# marty.net
KiCad netlist of a schematic drawn in EAGLE
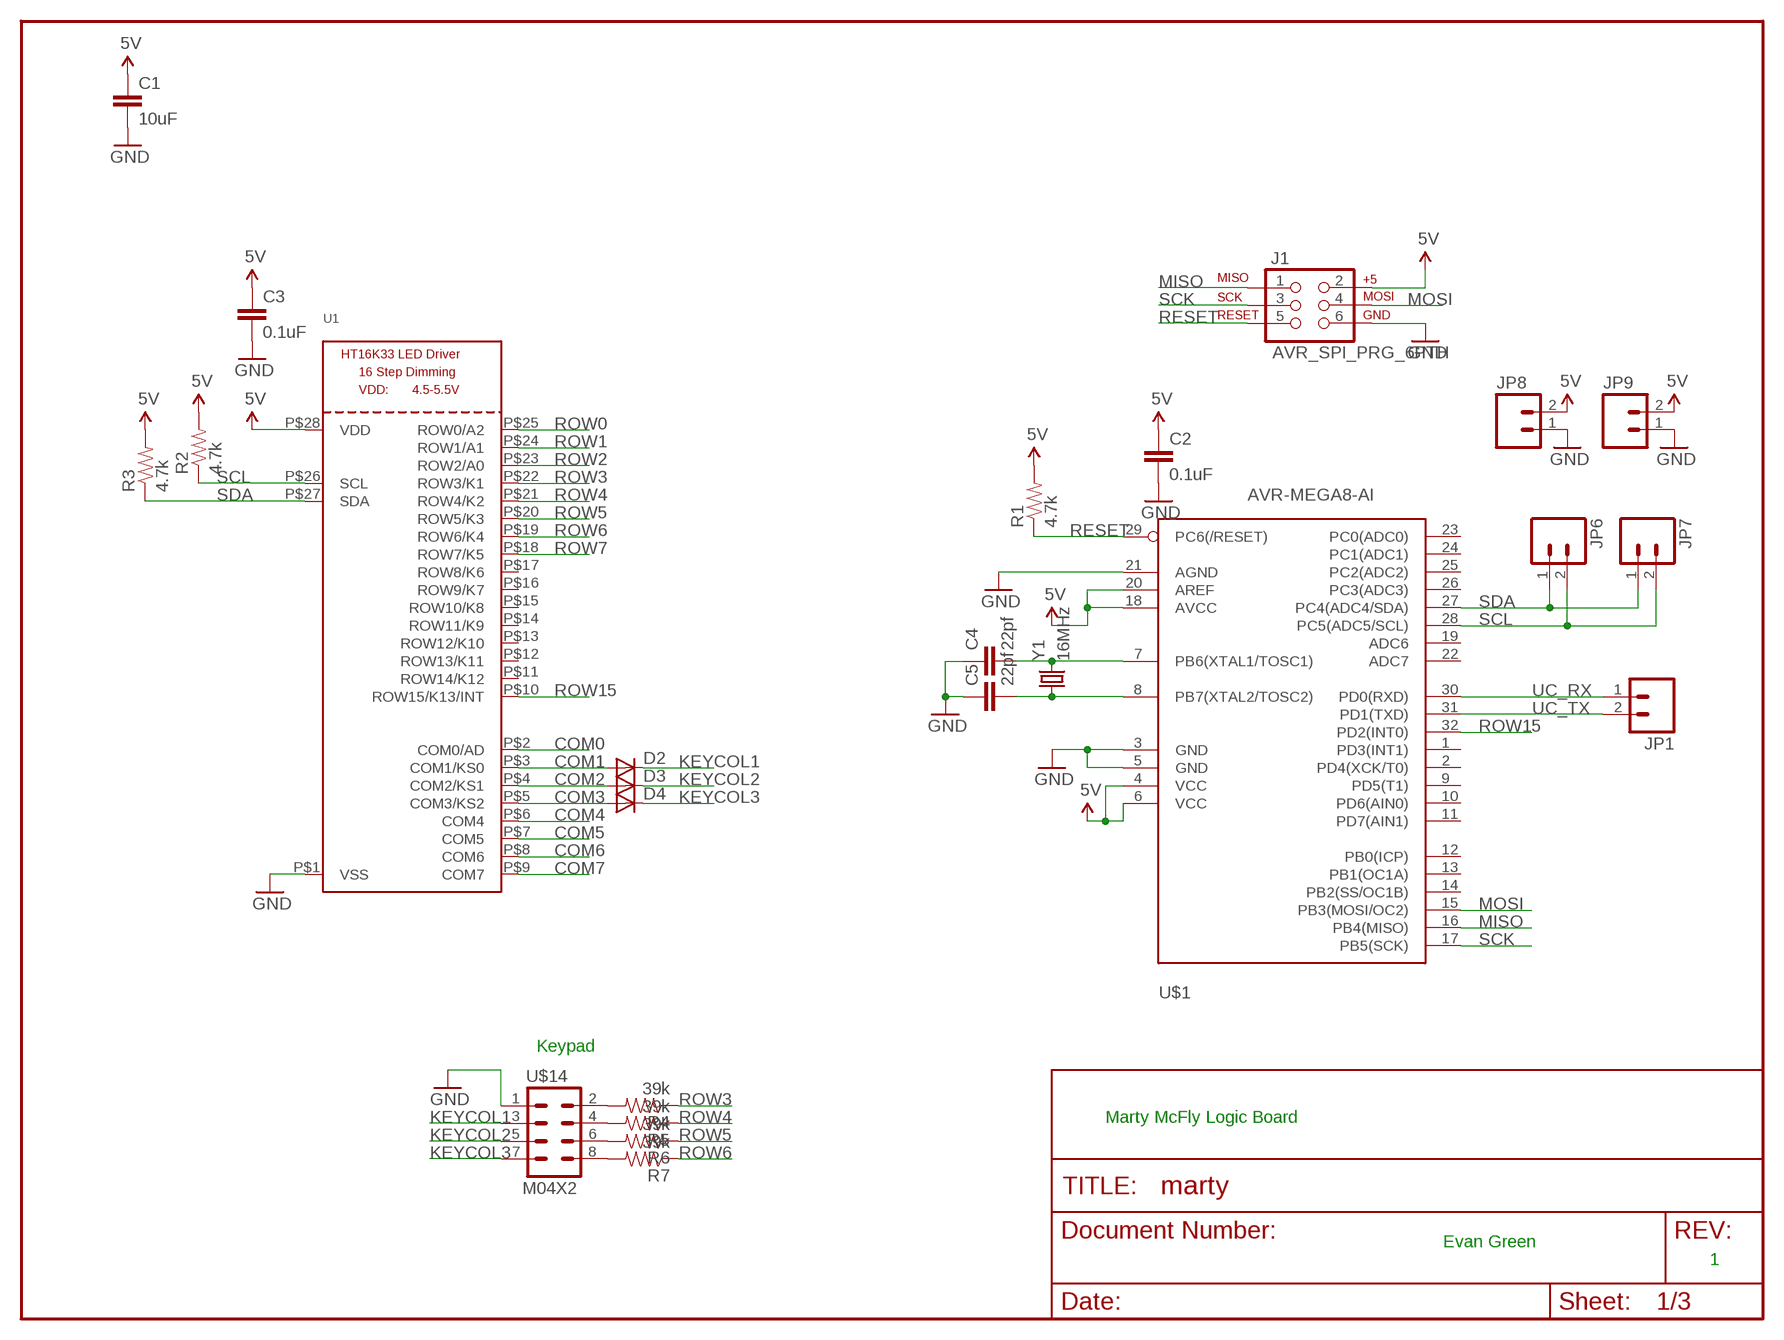
[diagram p0: schematic, sheet 1]
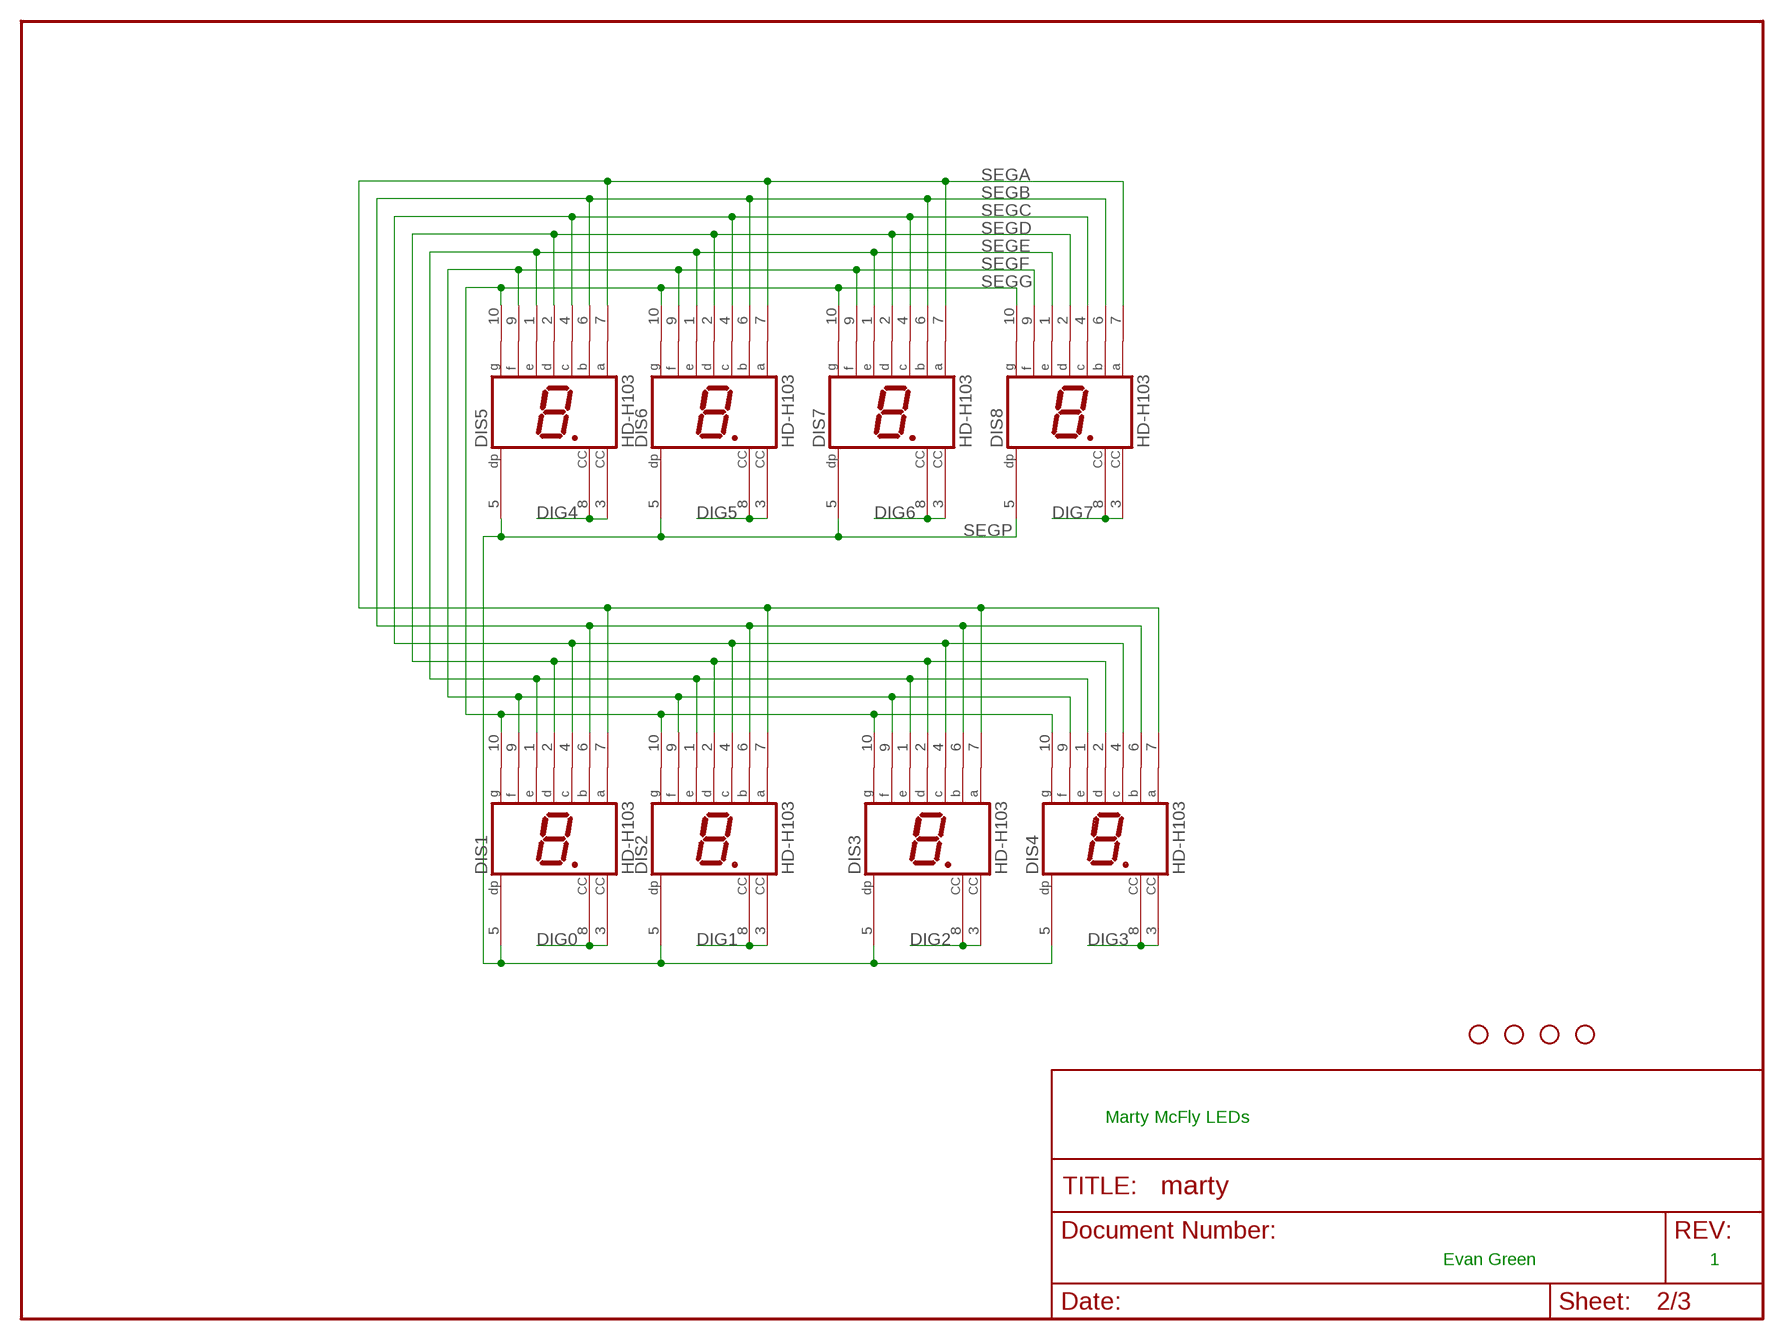
[diagram p1: schematic, sheet 2]
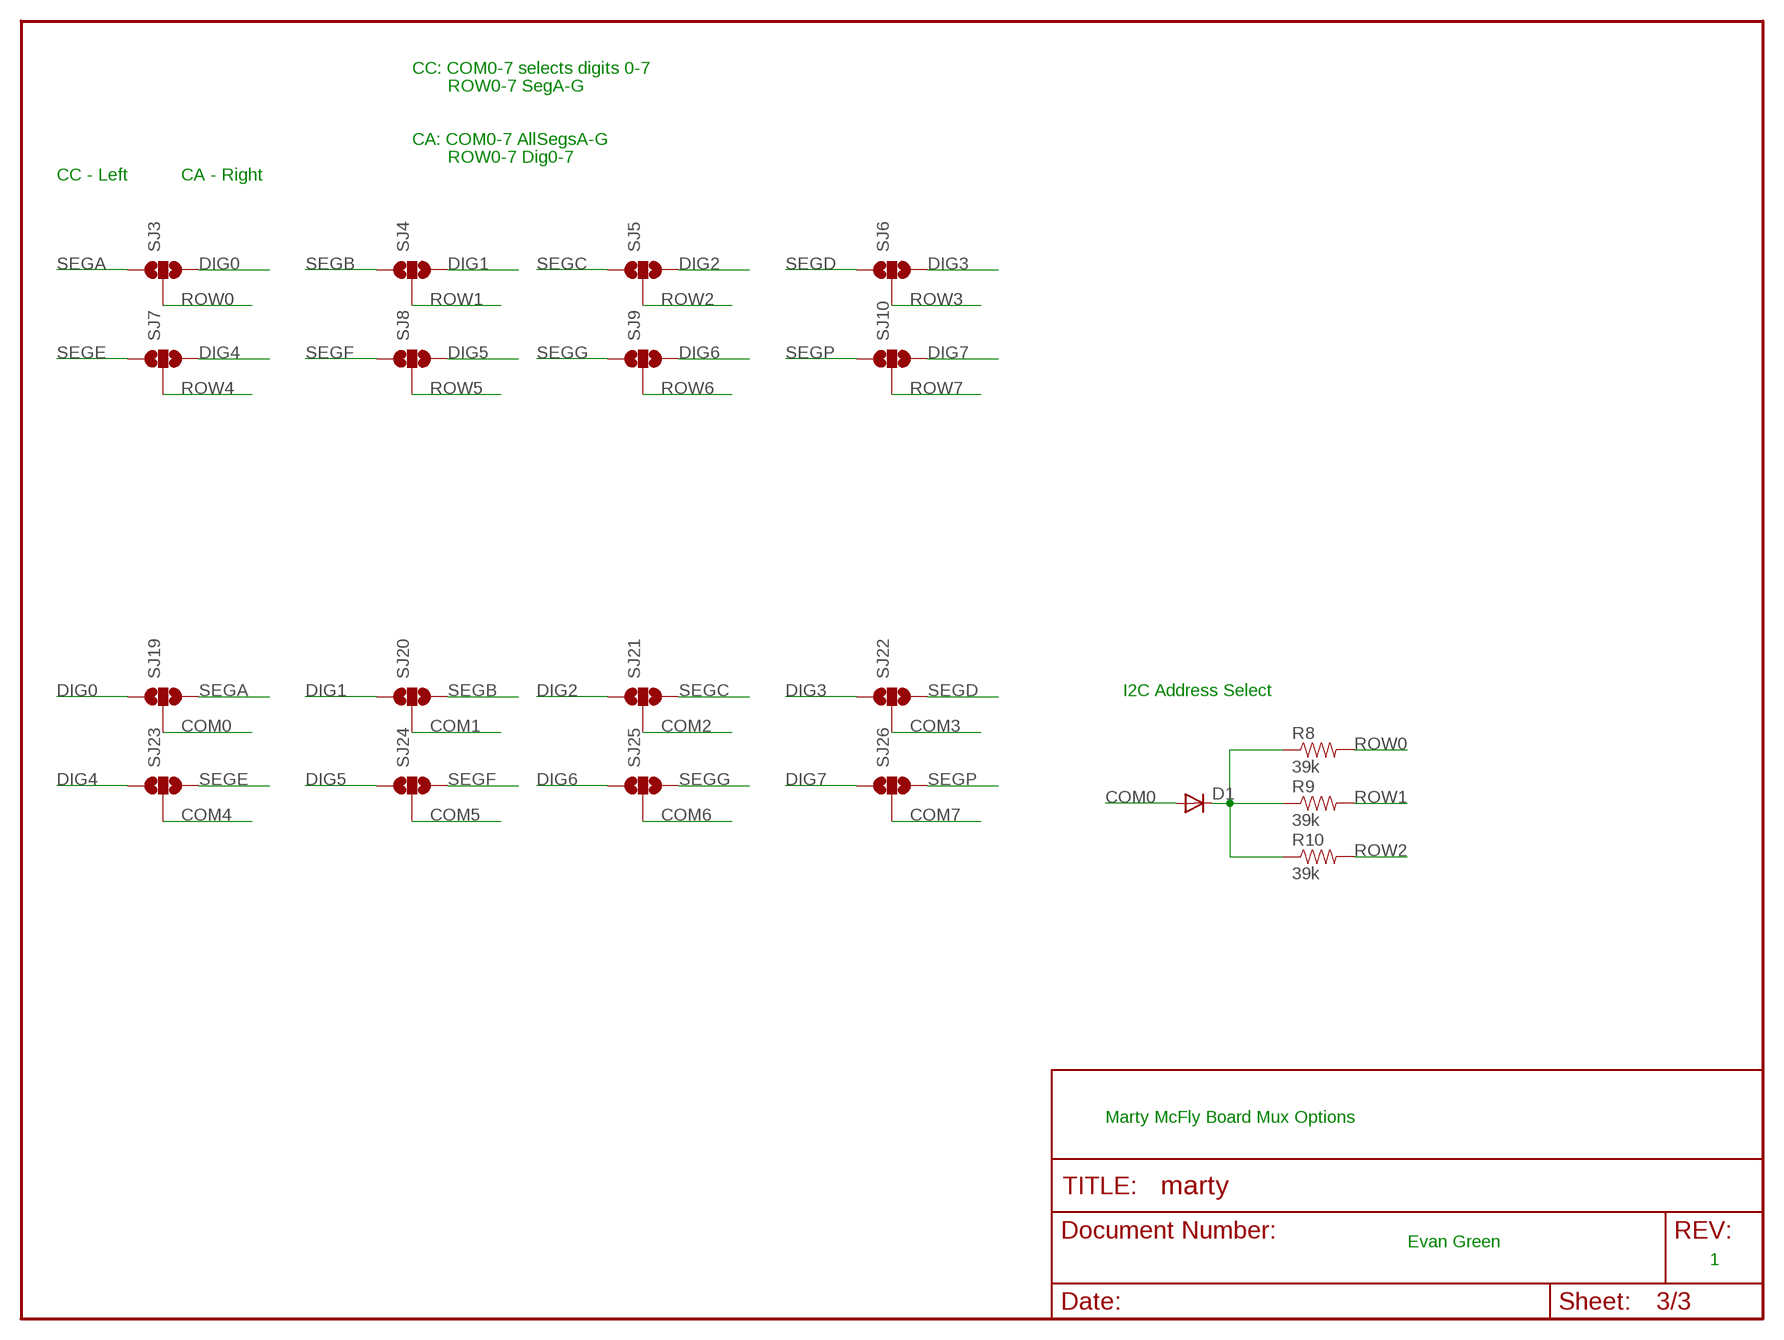
[diagram p2: schematic, sheet 3]

(export (version "E")
  (design (tool "Eeschema 10.0.6"))
  (components
    (comp (ref "C1")
      (value "10uF")
      (footprint "eagle-import:1210")
      (libsource (lib "eagle-import") (part "CAP1210"))
    )
    (comp (ref "C2")
      (value "0.1uF")
      (footprint "eagle-import:0402-CAP")
      (libsource (lib "eagle-import") (part "CAP0402-CAP"))
    )
    (comp (ref "C3")
      (value "0.1uF")
      (footprint "eagle-import:0402-CAP")
      (libsource (lib "eagle-import") (part "CAP0402-CAP"))
    )
    (comp (ref "C4")
      (value "22pf")
      (footprint "eagle-import:0402-CAP")
      (libsource (lib "eagle-import") (part "CAP0402-CAP"))
    )
    (comp (ref "C5")
      (value "22pf")
      (footprint "eagle-import:0402-CAP")
      (libsource (lib "eagle-import") (part "CAP0402-CAP"))
    )
    (comp (ref "D2")
      (value "DIODESOD")
      (footprint "eagle-import:SOD-323")
      (libsource (lib "eagle-import") (part "DIODESOD"))
    )
    (comp (ref "D3")
      (value "DIODESOD")
      (footprint "eagle-import:SOD-323")
      (libsource (lib "eagle-import") (part "DIODESOD"))
    )
    (comp (ref "D4")
      (value "DIODESOD")
      (footprint "eagle-import:SOD-323")
      (libsource (lib "eagle-import") (part "DIODESOD"))
    )
    (comp (ref "J1")
      (value "AVR_SPI_PRG_6PTH")
      (footprint "eagle-import:2X3")
      (libsource (lib "eagle-import") (part "AVR_SPI_PRG_6PTH"))
    )
    (comp (ref "JP1")
      (value "M02PTH")
      (footprint "eagle-import:1X02")
      (libsource (lib "eagle-import") (part "M02PTH"))
    )
    (comp (ref "JP6")
      (value "M02PTH")
      (footprint "eagle-import:1X02")
      (libsource (lib "eagle-import") (part "M02PTH"))
    )
    (comp (ref "JP7")
      (value "M02PTH")
      (footprint "eagle-import:1X02")
      (libsource (lib "eagle-import") (part "M02PTH"))
    )
    (comp (ref "JP8")
      (value "M02PTH")
      (footprint "eagle-import:1X02")
      (libsource (lib "eagle-import") (part "M02PTH"))
    )
    (comp (ref "JP9")
      (value "M02PTH")
      (footprint "eagle-import:1X02")
      (libsource (lib "eagle-import") (part "M02PTH"))
    )
    (comp (ref "R1")
      (value "4.7k")
      (footprint "eagle-import:0402-RES")
      (libsource (lib "eagle-import") (part "RESISTOR0402-RES"))
    )
    (comp (ref "R2")
      (value "4.7k")
      (footprint "eagle-import:0402-RES")
      (libsource (lib "eagle-import") (part "RESISTOR0402-RES"))
    )
    (comp (ref "R3")
      (value "4.7k")
      (footprint "eagle-import:0402-RES")
      (libsource (lib "eagle-import") (part "RESISTOR0402-RES"))
    )
    (comp (ref "R4")
      (value "39k")
      (footprint "eagle-import:0402-RES")
      (libsource (lib "eagle-import") (part "RESISTOR0402-RES"))
    )
    (comp (ref "R5")
      (value "39k")
      (footprint "eagle-import:0402-RES")
      (libsource (lib "eagle-import") (part "RESISTOR0402-RES"))
    )
    (comp (ref "R6")
      (value "39k")
      (footprint "eagle-import:0402-RES")
      (libsource (lib "eagle-import") (part "RESISTOR0402-RES"))
    )
    (comp (ref "R7")
      (value "39k")
      (footprint "eagle-import:0402-RES")
      (libsource (lib "eagle-import") (part "RESISTOR0402-RES"))
    )
    (comp (ref "U$1")
      (value "AVR-MEGA8-AI")
      (footprint "eagle-import:TQFP32-08")
      (libsource (lib "eagle-import") (part "AVR-MEGA8-AI"))
    )
    (comp (ref "U$14")
      (value "M04X2")
      (footprint "eagle-import:2X4")
      (libsource (lib "eagle-import") (part "M04X2"))
    )
    (comp (ref "U1")
      (value "HT16K33_SOP28")
      (footprint "eagle-import:SOP28_300MIL")
      (libsource (lib "eagle-import") (part "HT16K33_SOP28"))
    )
    (comp (ref "Y1")
      (value "16MHz")
      (footprint "eagle-import:HC49US")
      (libsource (lib "eagle-import") (part "CRYSTALHC49US"))
    )
    (comp (ref "D1")
      (value "DIODESOD")
      (footprint "eagle-import:SOD-323")
      (libsource (lib "eagle-import") (part "DIODESOD"))
    )
    (comp (ref "R8")
      (value "39k")
      (footprint "eagle-import:0402-RES")
      (libsource (lib "eagle-import") (part "RESISTOR0402-RES"))
    )
    (comp (ref "R9")
      (value "39k")
      (footprint "eagle-import:0402-RES")
      (libsource (lib "eagle-import") (part "RESISTOR0402-RES"))
    )
    (comp (ref "R10")
      (value "39k")
      (footprint "eagle-import:0402-RES")
      (libsource (lib "eagle-import") (part "RESISTOR0402-RES"))
    )
    (comp (ref "SJ3")
      (value "SOLDERJUMPER_2WAYS")
      (footprint "eagle-import:SJ_3")
      (libsource (lib "eagle-import") (part "SOLDERJUMPER_2WAYS"))
    )
    (comp (ref "SJ4")
      (value "SOLDERJUMPER_2WAYS")
      (footprint "eagle-import:SJ_3")
      (libsource (lib "eagle-import") (part "SOLDERJUMPER_2WAYS"))
    )
    (comp (ref "SJ5")
      (value "SOLDERJUMPER_2WAYS")
      (footprint "eagle-import:SJ_3")
      (libsource (lib "eagle-import") (part "SOLDERJUMPER_2WAYS"))
    )
    (comp (ref "SJ6")
      (value "SOLDERJUMPER_2WAYS")
      (footprint "eagle-import:SJ_3")
      (libsource (lib "eagle-import") (part "SOLDERJUMPER_2WAYS"))
    )
    (comp (ref "SJ7")
      (value "SOLDERJUMPER_2WAYS")
      (footprint "eagle-import:SJ_3")
      (libsource (lib "eagle-import") (part "SOLDERJUMPER_2WAYS"))
    )
    (comp (ref "SJ8")
      (value "SOLDERJUMPER_2WAYS")
      (footprint "eagle-import:SJ_3")
      (libsource (lib "eagle-import") (part "SOLDERJUMPER_2WAYS"))
    )
    (comp (ref "SJ9")
      (value "SOLDERJUMPER_2WAYS")
      (footprint "eagle-import:SJ_3")
      (libsource (lib "eagle-import") (part "SOLDERJUMPER_2WAYS"))
    )
    (comp (ref "SJ10")
      (value "SOLDERJUMPER_2WAYS")
      (footprint "eagle-import:SJ_3")
      (libsource (lib "eagle-import") (part "SOLDERJUMPER_2WAYS"))
    )
    (comp (ref "SJ19")
      (value "SOLDERJUMPER_2WAYS")
      (footprint "eagle-import:SJ_3")
      (libsource (lib "eagle-import") (part "SOLDERJUMPER_2WAYS"))
    )
    (comp (ref "SJ20")
      (value "SOLDERJUMPER_2WAYS")
      (footprint "eagle-import:SJ_3")
      (libsource (lib "eagle-import") (part "SOLDERJUMPER_2WAYS"))
    )
    (comp (ref "SJ21")
      (value "SOLDERJUMPER_2WAYS")
      (footprint "eagle-import:SJ_3")
      (libsource (lib "eagle-import") (part "SOLDERJUMPER_2WAYS"))
    )
    (comp (ref "SJ22")
      (value "SOLDERJUMPER_2WAYS")
      (footprint "eagle-import:SJ_3")
      (libsource (lib "eagle-import") (part "SOLDERJUMPER_2WAYS"))
    )
    (comp (ref "SJ23")
      (value "SOLDERJUMPER_2WAYS")
      (footprint "eagle-import:SJ_3")
      (libsource (lib "eagle-import") (part "SOLDERJUMPER_2WAYS"))
    )
    (comp (ref "SJ24")
      (value "SOLDERJUMPER_2WAYS")
      (footprint "eagle-import:SJ_3")
      (libsource (lib "eagle-import") (part "SOLDERJUMPER_2WAYS"))
    )
    (comp (ref "SJ25")
      (value "SOLDERJUMPER_2WAYS")
      (footprint "eagle-import:SJ_3")
      (libsource (lib "eagle-import") (part "SOLDERJUMPER_2WAYS"))
    )
    (comp (ref "SJ26")
      (value "SOLDERJUMPER_2WAYS")
      (footprint "eagle-import:SJ_3")
      (libsource (lib "eagle-import") (part "SOLDERJUMPER_2WAYS"))
    )
    (comp (ref "DIS1")
      (value "HD-H103")
      (footprint "eagle-import:HDSP-M")
      (libsource (lib "eagle-import") (part "HD-H103"))
    )
    (comp (ref "DIS2")
      (value "HD-H103")
      (footprint "eagle-import:HDSP-M")
      (libsource (lib "eagle-import") (part "HD-H103"))
    )
    (comp (ref "DIS3")
      (value "HD-H103")
      (footprint "eagle-import:HDSP-M")
      (libsource (lib "eagle-import") (part "HD-H103"))
    )
    (comp (ref "DIS4")
      (value "HD-H103")
      (footprint "eagle-import:HDSP-M")
      (libsource (lib "eagle-import") (part "HD-H103"))
    )
    (comp (ref "DIS5")
      (value "HD-H103")
      (footprint "eagle-import:HDSP-M")
      (libsource (lib "eagle-import") (part "HD-H103"))
    )
    (comp (ref "DIS6")
      (value "HD-H103")
      (footprint "eagle-import:HDSP-M")
      (libsource (lib "eagle-import") (part "HD-H103"))
    )
    (comp (ref "DIS7")
      (value "HD-H103")
      (footprint "eagle-import:HDSP-M")
      (libsource (lib "eagle-import") (part "HD-H103"))
    )
    (comp (ref "DIS8")
      (value "HD-H103")
      (footprint "eagle-import:HDSP-M")
      (libsource (lib "eagle-import") (part "HD-H103"))
    )
    (comp (ref "JP2")
      (value "STAND-OFF")
      (footprint "eagle-import:STAND-OFF")
      (libsource (lib "eagle-import") (part "STAND-OFF"))
    )
    (comp (ref "JP3")
      (value "STAND-OFF")
      (footprint "eagle-import:STAND-OFF")
      (libsource (lib "eagle-import") (part "STAND-OFF"))
    )
    (comp (ref "JP4")
      (value "STAND-OFF")
      (footprint "eagle-import:STAND-OFF")
      (libsource (lib "eagle-import") (part "STAND-OFF"))
    )
    (comp (ref "JP5")
      (value "STAND-OFF")
      (footprint "eagle-import:STAND-OFF")
      (libsource (lib "eagle-import") (part "STAND-OFF"))
    )
  )
  (nets
    (net (code "1") (name "5V") (class "Default")
      (node (ref "C1") (pin "1") (pinfunction "1_1") (pintype "passive"))
      (node (ref "C2") (pin "1") (pinfunction "1_1") (pintype "passive"))
      (node (ref "C3") (pin "1") (pinfunction "1_1") (pintype "passive"))
      (node (ref "J1") (pin "2") (pinfunction "2_2") (pintype "passive"))
      (node (ref "JP8") (pin "2") (pinfunction "2_2") (pintype "passive"))
      (node (ref "JP9") (pin "2") (pinfunction "2_2") (pintype "passive"))
      (node (ref "R1") (pin "2") (pinfunction "2_2") (pintype "passive"))
      (node (ref "R2") (pin "2") (pinfunction "2_2") (pintype "passive"))
      (node (ref "R3") (pin "2") (pinfunction "2_2") (pintype "passive"))
      (node (ref "U$1") (pin "18") (pinfunction "AVCC_18") (pintype "bidirectional"))
      (node (ref "U$1") (pin "20") (pinfunction "AREF_20") (pintype "bidirectional"))
      (node (ref "U$1") (pin "4") (pinfunction "VCC_4") (pintype "bidirectional"))
      (node (ref "U$1") (pin "6") (pinfunction "VCC_6") (pintype "bidirectional"))
      (node (ref "U1") (pin "P$28") (pinfunction "VDD_P$28") (pintype "bidirectional"))
    )
    (net (code "2") (name "COM0") (class "Default")
      (node (ref "D1") (pin "2") (pinfunction "A_2") (pintype "passive"))
      (node (ref "SJ19") (pin "2") (pinfunction "2_2") (pintype "passive"))
      (node (ref "U1") (pin "P$2") (pinfunction "COM0/AD_P$2") (pintype "bidirectional"))
    )
    (net (code "3") (name "COM1") (class "Default")
      (node (ref "D2") (pin "2") (pinfunction "A_2") (pintype "passive"))
      (node (ref "SJ20") (pin "2") (pinfunction "2_2") (pintype "passive"))
      (node (ref "U1") (pin "P$3") (pinfunction "COM1/KS0_P$3") (pintype "bidirectional"))
    )
    (net (code "4") (name "COM2") (class "Default")
      (node (ref "D3") (pin "2") (pinfunction "A_2") (pintype "passive"))
      (node (ref "SJ21") (pin "2") (pinfunction "2_2") (pintype "passive"))
      (node (ref "U1") (pin "P$4") (pinfunction "COM2/KS1_P$4") (pintype "bidirectional"))
    )
    (net (code "5") (name "COM3") (class "Default")
      (node (ref "D4") (pin "2") (pinfunction "A_2") (pintype "passive"))
      (node (ref "SJ22") (pin "2") (pinfunction "2_2") (pintype "passive"))
      (node (ref "U1") (pin "P$5") (pinfunction "COM3/KS2_P$5") (pintype "bidirectional"))
    )
    (net (code "6") (name "COM4") (class "Default")
      (node (ref "SJ23") (pin "2") (pinfunction "2_2") (pintype "passive"))
      (node (ref "U1") (pin "P$6") (pinfunction "COM4_P$6") (pintype "bidirectional"))
    )
    (net (code "7") (name "COM5") (class "Default")
      (node (ref "SJ24") (pin "2") (pinfunction "2_2") (pintype "passive"))
      (node (ref "U1") (pin "P$7") (pinfunction "COM5_P$7") (pintype "bidirectional"))
    )
    (net (code "8") (name "COM6") (class "Default")
      (node (ref "SJ25") (pin "2") (pinfunction "2_2") (pintype "passive"))
      (node (ref "U1") (pin "P$8") (pinfunction "COM6_P$8") (pintype "bidirectional"))
    )
    (net (code "9") (name "COM7") (class "Default")
      (node (ref "SJ26") (pin "2") (pinfunction "2_2") (pintype "passive"))
      (node (ref "U1") (pin "P$9") (pinfunction "COM7_P$9") (pintype "bidirectional"))
    )
    (net (code "10") (name "DIG0") (class "Default")
      (node (ref "DIS1") (pin "3") (pinfunction "CC_3") (pintype "passive"))
      (node (ref "DIS1") (pin "8") (pinfunction "CC_8") (pintype "passive"))
      (node (ref "SJ19") (pin "1") (pinfunction "1_1") (pintype "passive"))
      (node (ref "SJ3") (pin "3") (pinfunction "3_3") (pintype "passive"))
    )
    (net (code "11") (name "DIG1") (class "Default")
      (node (ref "DIS2") (pin "3") (pinfunction "CC_3") (pintype "passive"))
      (node (ref "DIS2") (pin "8") (pinfunction "CC_8") (pintype "passive"))
      (node (ref "SJ20") (pin "1") (pinfunction "1_1") (pintype "passive"))
      (node (ref "SJ4") (pin "3") (pinfunction "3_3") (pintype "passive"))
    )
    (net (code "12") (name "DIG2") (class "Default")
      (node (ref "DIS3") (pin "3") (pinfunction "CC_3") (pintype "passive"))
      (node (ref "DIS3") (pin "8") (pinfunction "CC_8") (pintype "passive"))
      (node (ref "SJ21") (pin "1") (pinfunction "1_1") (pintype "passive"))
      (node (ref "SJ5") (pin "3") (pinfunction "3_3") (pintype "passive"))
    )
    (net (code "13") (name "DIG3") (class "Default")
      (node (ref "DIS4") (pin "3") (pinfunction "CC_3") (pintype "passive"))
      (node (ref "DIS4") (pin "8") (pinfunction "CC_8") (pintype "passive"))
      (node (ref "SJ22") (pin "1") (pinfunction "1_1") (pintype "passive"))
      (node (ref "SJ6") (pin "3") (pinfunction "3_3") (pintype "passive"))
    )
    (net (code "14") (name "DIG4") (class "Default")
      (node (ref "DIS5") (pin "3") (pinfunction "CC_3") (pintype "passive"))
      (node (ref "DIS5") (pin "8") (pinfunction "CC_8") (pintype "passive"))
      (node (ref "SJ23") (pin "1") (pinfunction "1_1") (pintype "passive"))
      (node (ref "SJ7") (pin "3") (pinfunction "3_3") (pintype "passive"))
    )
    (net (code "15") (name "DIG5") (class "Default")
      (node (ref "DIS6") (pin "3") (pinfunction "CC_3") (pintype "passive"))
      (node (ref "DIS6") (pin "8") (pinfunction "CC_8") (pintype "passive"))
      (node (ref "SJ24") (pin "1") (pinfunction "1_1") (pintype "passive"))
      (node (ref "SJ8") (pin "3") (pinfunction "3_3") (pintype "passive"))
    )
    (net (code "16") (name "DIG6") (class "Default")
      (node (ref "DIS7") (pin "3") (pinfunction "CC_3") (pintype "passive"))
      (node (ref "DIS7") (pin "8") (pinfunction "CC_8") (pintype "passive"))
      (node (ref "SJ25") (pin "1") (pinfunction "1_1") (pintype "passive"))
      (node (ref "SJ9") (pin "3") (pinfunction "3_3") (pintype "passive"))
    )
    (net (code "17") (name "DIG7") (class "Default")
      (node (ref "DIS8") (pin "3") (pinfunction "CC_3") (pintype "passive"))
      (node (ref "DIS8") (pin "8") (pinfunction "CC_8") (pintype "passive"))
      (node (ref "SJ10") (pin "3") (pinfunction "3_3") (pintype "passive"))
      (node (ref "SJ26") (pin "1") (pinfunction "1_1") (pintype "passive"))
    )
    (net (code "18") (name "GND") (class "Default")
      (node (ref "C1") (pin "2") (pinfunction "2_2") (pintype "passive"))
      (node (ref "C2") (pin "2") (pinfunction "2_2") (pintype "passive"))
      (node (ref "C3") (pin "2") (pinfunction "2_2") (pintype "passive"))
      (node (ref "C4") (pin "1") (pinfunction "1_1") (pintype "passive"))
      (node (ref "C5") (pin "1") (pinfunction "1_1") (pintype "passive"))
      (node (ref "J1") (pin "6") (pinfunction "6_6") (pintype "passive"))
      (node (ref "JP8") (pin "1") (pinfunction "1_1") (pintype "passive"))
      (node (ref "JP9") (pin "1") (pinfunction "1_1") (pintype "passive"))
      (node (ref "U$1") (pin "21") (pinfunction "AGND_21") (pintype "bidirectional"))
      (node (ref "U$1") (pin "3") (pinfunction "GND_3") (pintype "bidirectional"))
      (node (ref "U$1") (pin "5") (pinfunction "GND_5") (pintype "bidirectional"))
      (node (ref "U$14") (pin "1") (pinfunction "1_1") (pintype "passive"))
      (node (ref "U1") (pin "P$1") (pinfunction "VSS_P$1") (pintype "bidirectional"))
    )
    (net (code "19") (name "KEYCOL1") (class "Default")
      (node (ref "D2") (pin "1") (pinfunction "C_1") (pintype "passive"))
      (node (ref "U$14") (pin "3") (pinfunction "3_3") (pintype "passive"))
    )
    (net (code "20") (name "KEYCOL2") (class "Default")
      (node (ref "D3") (pin "1") (pinfunction "C_1") (pintype "passive"))
      (node (ref "U$14") (pin "5") (pinfunction "5_5") (pintype "passive"))
    )
    (net (code "21") (name "KEYCOL3") (class "Default")
      (node (ref "D4") (pin "1") (pinfunction "C_1") (pintype "passive"))
      (node (ref "U$14") (pin "7") (pinfunction "7_7") (pintype "passive"))
    )
    (net (code "22") (name "MISO") (class "Default")
      (node (ref "J1") (pin "1") (pinfunction "1_1") (pintype "passive"))
      (node (ref "U$1") (pin "16") (pinfunction "PB4(MISO)_16") (pintype "bidirectional"))
    )
    (net (code "23") (name "MOSI") (class "Default")
      (node (ref "J1") (pin "4") (pinfunction "4_4") (pintype "passive"))
      (node (ref "U$1") (pin "15") (pinfunction "PB3(MOSI/OC2)_15") (pintype "bidirectional"))
    )
    (net (code "24") (name "Net-(D1-C)") (class "Default")
      (node (ref "D1") (pin "1") (pinfunction "C_1") (pintype "passive"))
      (node (ref "R10") (pin "1") (pinfunction "1_1") (pintype "passive"))
      (node (ref "R8") (pin "1") (pinfunction "1_1") (pintype "passive"))
      (node (ref "R9") (pin "1") (pinfunction "1_1") (pintype "passive"))
    )
    (net (code "25") (name "Net-(R4-Pad2)") (class "Default")
      (node (ref "R4") (pin "2") (pinfunction "2_2") (pintype "passive"))
      (node (ref "U$14") (pin "2") (pinfunction "2_2") (pintype "passive"))
    )
    (net (code "26") (name "Net-(R5-Pad2)") (class "Default")
      (node (ref "R5") (pin "2") (pinfunction "2_2") (pintype "passive"))
      (node (ref "U$14") (pin "4") (pinfunction "4_4") (pintype "passive"))
    )
    (net (code "27") (name "Net-(R6-Pad2)") (class "Default")
      (node (ref "R6") (pin "2") (pinfunction "2_2") (pintype "passive"))
      (node (ref "U$14") (pin "6") (pinfunction "6_6") (pintype "passive"))
    )
    (net (code "28") (name "Net-(R7-Pad2)") (class "Default")
      (node (ref "R7") (pin "2") (pinfunction "2_2") (pintype "passive"))
      (node (ref "U$14") (pin "8") (pinfunction "8_8") (pintype "passive"))
    )
    (net (code "29") (name "Net-(U$1-PB6(XTAL1{slash}TOSC1))") (class "Default")
      (node (ref "C4") (pin "2") (pinfunction "2_2") (pintype "passive"))
      (node (ref "U$1") (pin "7") (pinfunction "PB6(XTAL1/TOSC1)_7") (pintype "bidirectional"))
      (node (ref "Y1") (pin "2") (pinfunction "2_2") (pintype "passive"))
    )
    (net (code "30") (name "Net-(U$1-PB7(XTAL2{slash}TOSC2))") (class "Default")
      (node (ref "C5") (pin "2") (pinfunction "2_2") (pintype "passive"))
      (node (ref "U$1") (pin "8") (pinfunction "PB7(XTAL2/TOSC2)_8") (pintype "bidirectional"))
      (node (ref "Y1") (pin "1") (pinfunction "1_1") (pintype "passive"))
    )
    (net (code "31") (name "RESET") (class "Default")
      (node (ref "J1") (pin "5") (pinfunction "5_5") (pintype "passive"))
      (node (ref "R1") (pin "1") (pinfunction "1_1") (pintype "passive"))
      (node (ref "U$1") (pin "29") (pinfunction "PC6(/RESET)_29") (pintype "bidirectional"))
    )
    (net (code "32") (name "ROW0") (class "Default")
      (node (ref "R8") (pin "2") (pinfunction "2_2") (pintype "passive"))
      (node (ref "SJ3") (pin "2") (pinfunction "2_2") (pintype "passive"))
      (node (ref "U1") (pin "P$25") (pinfunction "ROW0/A2_P$25") (pintype "bidirectional"))
    )
    (net (code "33") (name "ROW1") (class "Default")
      (node (ref "R9") (pin "2") (pinfunction "2_2") (pintype "passive"))
      (node (ref "SJ4") (pin "2") (pinfunction "2_2") (pintype "passive"))
      (node (ref "U1") (pin "P$24") (pinfunction "ROW1/A1_P$24") (pintype "bidirectional"))
    )
    (net (code "34") (name "ROW2") (class "Default")
      (node (ref "R10") (pin "2") (pinfunction "2_2") (pintype "passive"))
      (node (ref "SJ5") (pin "2") (pinfunction "2_2") (pintype "passive"))
      (node (ref "U1") (pin "P$23") (pinfunction "ROW2/A0_P$23") (pintype "bidirectional"))
    )
    (net (code "35") (name "ROW3") (class "Default")
      (node (ref "R4") (pin "1") (pinfunction "1_1") (pintype "passive"))
      (node (ref "SJ6") (pin "2") (pinfunction "2_2") (pintype "passive"))
      (node (ref "U1") (pin "P$22") (pinfunction "ROW3/K1_P$22") (pintype "bidirectional"))
    )
    (net (code "36") (name "ROW4") (class "Default")
      (node (ref "R5") (pin "1") (pinfunction "1_1") (pintype "passive"))
      (node (ref "SJ7") (pin "2") (pinfunction "2_2") (pintype "passive"))
      (node (ref "U1") (pin "P$21") (pinfunction "ROW4/K2_P$21") (pintype "bidirectional"))
    )
    (net (code "37") (name "ROW5") (class "Default")
      (node (ref "R6") (pin "1") (pinfunction "1_1") (pintype "passive"))
      (node (ref "SJ8") (pin "2") (pinfunction "2_2") (pintype "passive"))
      (node (ref "U1") (pin "P$20") (pinfunction "ROW5/K3_P$20") (pintype "bidirectional"))
    )
    (net (code "38") (name "ROW6") (class "Default")
      (node (ref "R7") (pin "1") (pinfunction "1_1") (pintype "passive"))
      (node (ref "SJ9") (pin "2") (pinfunction "2_2") (pintype "passive"))
      (node (ref "U1") (pin "P$19") (pinfunction "ROW6/K4_P$19") (pintype "bidirectional"))
    )
    (net (code "39") (name "ROW7") (class "Default")
      (node (ref "SJ10") (pin "2") (pinfunction "2_2") (pintype "passive"))
      (node (ref "U1") (pin "P$18") (pinfunction "ROW7/K5_P$18") (pintype "bidirectional"))
    )
    (net (code "40") (name "ROW15") (class "Default")
      (node (ref "U$1") (pin "32") (pinfunction "PD2(INT0)_32") (pintype "bidirectional"))
      (node (ref "U1") (pin "P$10") (pinfunction "ROW15/K13/INT_P$10") (pintype "bidirectional"))
    )
    (net (code "41") (name "SCK") (class "Default")
      (node (ref "J1") (pin "3") (pinfunction "3_3") (pintype "passive"))
      (node (ref "U$1") (pin "17") (pinfunction "PB5(SCK)_17") (pintype "bidirectional"))
    )
    (net (code "42") (name "SCL") (class "Default")
      (node (ref "JP6") (pin "2") (pinfunction "2_2") (pintype "passive"))
      (node (ref "JP7") (pin "2") (pinfunction "2_2") (pintype "passive"))
      (node (ref "R2") (pin "1") (pinfunction "1_1") (pintype "passive"))
      (node (ref "U$1") (pin "28") (pinfunction "PC5(ADC5/SCL)_28") (pintype "bidirectional"))
      (node (ref "U1") (pin "P$26") (pinfunction "SCL_P$26") (pintype "bidirectional"))
    )
    (net (code "43") (name "SDA") (class "Default")
      (node (ref "JP6") (pin "1") (pinfunction "1_1") (pintype "passive"))
      (node (ref "JP7") (pin "1") (pinfunction "1_1") (pintype "passive"))
      (node (ref "R3") (pin "1") (pinfunction "1_1") (pintype "passive"))
      (node (ref "U$1") (pin "27") (pinfunction "PC4(ADC4/SDA)_27") (pintype "bidirectional"))
      (node (ref "U1") (pin "P$27") (pinfunction "SDA_P$27") (pintype "bidirectional"))
    )
    (net (code "44") (name "SEGA") (class "Default")
      (node (ref "DIS1") (pin "7") (pinfunction "A_7") (pintype "passive"))
      (node (ref "DIS2") (pin "7") (pinfunction "A_7") (pintype "passive"))
      (node (ref "DIS3") (pin "7") (pinfunction "A_7") (pintype "passive"))
      (node (ref "DIS4") (pin "7") (pinfunction "A_7") (pintype "passive"))
      (node (ref "DIS5") (pin "7") (pinfunction "A_7") (pintype "passive"))
      (node (ref "DIS6") (pin "7") (pinfunction "A_7") (pintype "passive"))
      (node (ref "DIS7") (pin "7") (pinfunction "A_7") (pintype "passive"))
      (node (ref "DIS8") (pin "7") (pinfunction "A_7") (pintype "passive"))
      (node (ref "SJ19") (pin "3") (pinfunction "3_3") (pintype "passive"))
      (node (ref "SJ3") (pin "1") (pinfunction "1_1") (pintype "passive"))
    )
    (net (code "45") (name "SEGB") (class "Default")
      (node (ref "DIS1") (pin "6") (pinfunction "B_6") (pintype "passive"))
      (node (ref "DIS2") (pin "6") (pinfunction "B_6") (pintype "passive"))
      (node (ref "DIS3") (pin "6") (pinfunction "B_6") (pintype "passive"))
      (node (ref "DIS4") (pin "6") (pinfunction "B_6") (pintype "passive"))
      (node (ref "DIS5") (pin "6") (pinfunction "B_6") (pintype "passive"))
      (node (ref "DIS6") (pin "6") (pinfunction "B_6") (pintype "passive"))
      (node (ref "DIS7") (pin "6") (pinfunction "B_6") (pintype "passive"))
      (node (ref "DIS8") (pin "6") (pinfunction "B_6") (pintype "passive"))
      (node (ref "SJ20") (pin "3") (pinfunction "3_3") (pintype "passive"))
      (node (ref "SJ4") (pin "1") (pinfunction "1_1") (pintype "passive"))
    )
    (net (code "46") (name "SEGC") (class "Default")
      (node (ref "DIS1") (pin "4") (pinfunction "C_4") (pintype "passive"))
      (node (ref "DIS2") (pin "4") (pinfunction "C_4") (pintype "passive"))
      (node (ref "DIS3") (pin "4") (pinfunction "C_4") (pintype "passive"))
      (node (ref "DIS4") (pin "4") (pinfunction "C_4") (pintype "passive"))
      (node (ref "DIS5") (pin "4") (pinfunction "C_4") (pintype "passive"))
      (node (ref "DIS6") (pin "4") (pinfunction "C_4") (pintype "passive"))
      (node (ref "DIS7") (pin "4") (pinfunction "C_4") (pintype "passive"))
      (node (ref "DIS8") (pin "4") (pinfunction "C_4") (pintype "passive"))
      (node (ref "SJ21") (pin "3") (pinfunction "3_3") (pintype "passive"))
      (node (ref "SJ5") (pin "1") (pinfunction "1_1") (pintype "passive"))
    )
    (net (code "47") (name "SEGD") (class "Default")
      (node (ref "DIS1") (pin "2") (pinfunction "D_2") (pintype "passive"))
      (node (ref "DIS2") (pin "2") (pinfunction "D_2") (pintype "passive"))
      (node (ref "DIS3") (pin "2") (pinfunction "D_2") (pintype "passive"))
      (node (ref "DIS4") (pin "2") (pinfunction "D_2") (pintype "passive"))
      (node (ref "DIS5") (pin "2") (pinfunction "D_2") (pintype "passive"))
      (node (ref "DIS6") (pin "2") (pinfunction "D_2") (pintype "passive"))
      (node (ref "DIS7") (pin "2") (pinfunction "D_2") (pintype "passive"))
      (node (ref "DIS8") (pin "2") (pinfunction "D_2") (pintype "passive"))
      (node (ref "SJ22") (pin "3") (pinfunction "3_3") (pintype "passive"))
      (node (ref "SJ6") (pin "1") (pinfunction "1_1") (pintype "passive"))
    )
    (net (code "48") (name "SEGE") (class "Default")
      (node (ref "DIS1") (pin "1") (pinfunction "E_1") (pintype "passive"))
      (node (ref "DIS2") (pin "1") (pinfunction "E_1") (pintype "passive"))
      (node (ref "DIS3") (pin "1") (pinfunction "E_1") (pintype "passive"))
      (node (ref "DIS4") (pin "1") (pinfunction "E_1") (pintype "passive"))
      (node (ref "DIS5") (pin "1") (pinfunction "E_1") (pintype "passive"))
      (node (ref "DIS6") (pin "1") (pinfunction "E_1") (pintype "passive"))
      (node (ref "DIS7") (pin "1") (pinfunction "E_1") (pintype "passive"))
      (node (ref "DIS8") (pin "1") (pinfunction "E_1") (pintype "passive"))
      (node (ref "SJ23") (pin "3") (pinfunction "3_3") (pintype "passive"))
      (node (ref "SJ7") (pin "1") (pinfunction "1_1") (pintype "passive"))
    )
    (net (code "49") (name "SEGF") (class "Default")
      (node (ref "DIS1") (pin "9") (pinfunction "F_9") (pintype "passive"))
      (node (ref "DIS2") (pin "9") (pinfunction "F_9") (pintype "passive"))
      (node (ref "DIS3") (pin "9") (pinfunction "F_9") (pintype "passive"))
      (node (ref "DIS4") (pin "9") (pinfunction "F_9") (pintype "passive"))
      (node (ref "DIS5") (pin "9") (pinfunction "F_9") (pintype "passive"))
      (node (ref "DIS6") (pin "9") (pinfunction "F_9") (pintype "passive"))
      (node (ref "DIS7") (pin "9") (pinfunction "F_9") (pintype "passive"))
      (node (ref "DIS8") (pin "9") (pinfunction "F_9") (pintype "passive"))
      (node (ref "SJ24") (pin "3") (pinfunction "3_3") (pintype "passive"))
      (node (ref "SJ8") (pin "1") (pinfunction "1_1") (pintype "passive"))
    )
    (net (code "50") (name "SEGG") (class "Default")
      (node (ref "DIS1") (pin "10") (pinfunction "G_10") (pintype "passive"))
      (node (ref "DIS2") (pin "10") (pinfunction "G_10") (pintype "passive"))
      (node (ref "DIS3") (pin "10") (pinfunction "G_10") (pintype "passive"))
      (node (ref "DIS4") (pin "10") (pinfunction "G_10") (pintype "passive"))
      (node (ref "DIS5") (pin "10") (pinfunction "G_10") (pintype "passive"))
      (node (ref "DIS6") (pin "10") (pinfunction "G_10") (pintype "passive"))
      (node (ref "DIS7") (pin "10") (pinfunction "G_10") (pintype "passive"))
      (node (ref "DIS8") (pin "10") (pinfunction "G_10") (pintype "passive"))
      (node (ref "SJ25") (pin "3") (pinfunction "3_3") (pintype "passive"))
      (node (ref "SJ9") (pin "1") (pinfunction "1_1") (pintype "passive"))
    )
    (net (code "51") (name "SEGP") (class "Default")
      (node (ref "DIS1") (pin "5") (pinfunction "DP_5") (pintype "passive"))
      (node (ref "DIS2") (pin "5") (pinfunction "DP_5") (pintype "passive"))
      (node (ref "DIS3") (pin "5") (pinfunction "DP_5") (pintype "passive"))
      (node (ref "DIS4") (pin "5") (pinfunction "DP_5") (pintype "passive"))
      (node (ref "DIS5") (pin "5") (pinfunction "DP_5") (pintype "passive"))
      (node (ref "DIS6") (pin "5") (pinfunction "DP_5") (pintype "passive"))
      (node (ref "DIS7") (pin "5") (pinfunction "DP_5") (pintype "passive"))
      (node (ref "DIS8") (pin "5") (pinfunction "DP_5") (pintype "passive"))
      (node (ref "SJ10") (pin "1") (pinfunction "1_1") (pintype "passive"))
      (node (ref "SJ26") (pin "3") (pinfunction "3_3") (pintype "passive"))
    )
    (net (code "52") (name "UC_RX") (class "Default")
      (node (ref "JP1") (pin "1") (pinfunction "1_1") (pintype "passive"))
      (node (ref "U$1") (pin "30") (pinfunction "PD0(RXD)_30") (pintype "bidirectional"))
    )
    (net (code "53") (name "UC_TX") (class "Default")
      (node (ref "JP1") (pin "2") (pinfunction "2_2") (pintype "passive"))
      (node (ref "U$1") (pin "31") (pinfunction "PD1(TXD)_31") (pintype "bidirectional"))
    )
    (net (code "54") (name "unconnected-(U$1-ADC6-Pad19)") (class "Default")
      (node (ref "U$1") (pin "19") (pinfunction "ADC6_19") (pintype "bidirectional"))
    )
    (net (code "55") (name "unconnected-(U$1-ADC7-Pad22)") (class "Default")
      (node (ref "U$1") (pin "22") (pinfunction "ADC7_22") (pintype "bidirectional"))
    )
    (net (code "56") (name "unconnected-(U$1-PB0(ICP)-Pad12)") (class "Default")
      (node (ref "U$1") (pin "12") (pinfunction "PB0(ICP)_12") (pintype "bidirectional"))
    )
    (net (code "57") (name "unconnected-(U$1-PB1(OC1A)-Pad13)") (class "Default")
      (node (ref "U$1") (pin "13") (pinfunction "PB1(OC1A)_13") (pintype "bidirectional"))
    )
    (net (code "58") (name "unconnected-(U$1-PB2(SS{slash}OC1B)-Pad14)") (class "Default")
      (node (ref "U$1") (pin "14") (pinfunction "PB2(SS/OC1B)_14") (pintype "bidirectional"))
    )
    (net (code "59") (name "unconnected-(U$1-PC0(ADC0)-Pad23)") (class "Default")
      (node (ref "U$1") (pin "23") (pinfunction "PC0(ADC0)_23") (pintype "bidirectional"))
    )
    (net (code "60") (name "unconnected-(U$1-PC1(ADC1)-Pad24)") (class "Default")
      (node (ref "U$1") (pin "24") (pinfunction "PC1(ADC1)_24") (pintype "bidirectional"))
    )
    (net (code "61") (name "unconnected-(U$1-PC2(ADC2)-Pad25)") (class "Default")
      (node (ref "U$1") (pin "25") (pinfunction "PC2(ADC2)_25") (pintype "bidirectional"))
    )
    (net (code "62") (name "unconnected-(U$1-PC3(ADC3)-Pad26)") (class "Default")
      (node (ref "U$1") (pin "26") (pinfunction "PC3(ADC3)_26") (pintype "bidirectional"))
    )
    (net (code "63") (name "unconnected-(U$1-PD3(INT1)-Pad1)") (class "Default")
      (node (ref "U$1") (pin "1") (pinfunction "PD3(INT1)_1") (pintype "bidirectional"))
    )
    (net (code "64") (name "unconnected-(U$1-PD4(XCK{slash}T0)-Pad2)") (class "Default")
      (node (ref "U$1") (pin "2") (pinfunction "PD4(XCK/T0)_2") (pintype "bidirectional"))
    )
    (net (code "65") (name "unconnected-(U$1-PD5(T1)-Pad9)") (class "Default")
      (node (ref "U$1") (pin "9") (pinfunction "PD5(T1)_9") (pintype "bidirectional"))
    )
    (net (code "66") (name "unconnected-(U$1-PD6(AIN0)-Pad10)") (class "Default")
      (node (ref "U$1") (pin "10") (pinfunction "PD6(AIN0)_10") (pintype "bidirectional"))
    )
    (net (code "67") (name "unconnected-(U$1-PD7(AIN1)-Pad11)") (class "Default")
      (node (ref "U$1") (pin "11") (pinfunction "PD7(AIN1)_11") (pintype "bidirectional"))
    )
    (net (code "68") (name "unconnected-(U1-ROW8{slash}K6-PadP$17)") (class "Default")
      (node (ref "U1") (pin "P$17") (pinfunction "ROW8/K6_P$17") (pintype "bidirectional"))
    )
    (net (code "69") (name "unconnected-(U1-ROW9{slash}K7-PadP$16)") (class "Default")
      (node (ref "U1") (pin "P$16") (pinfunction "ROW9/K7_P$16") (pintype "bidirectional"))
    )
    (net (code "70") (name "unconnected-(U1-ROW10{slash}K8-PadP$15)") (class "Default")
      (node (ref "U1") (pin "P$15") (pinfunction "ROW10/K8_P$15") (pintype "bidirectional"))
    )
    (net (code "71") (name "unconnected-(U1-ROW11{slash}K9-PadP$14)") (class "Default")
      (node (ref "U1") (pin "P$14") (pinfunction "ROW11/K9_P$14") (pintype "bidirectional"))
    )
    (net (code "72") (name "unconnected-(U1-ROW12{slash}K10-PadP$13)") (class "Default")
      (node (ref "U1") (pin "P$13") (pinfunction "ROW12/K10_P$13") (pintype "bidirectional"))
    )
    (net (code "73") (name "unconnected-(U1-ROW13{slash}K11-PadP$12)") (class "Default")
      (node (ref "U1") (pin "P$12") (pinfunction "ROW13/K11_P$12") (pintype "bidirectional"))
    )
    (net (code "74") (name "unconnected-(U1-ROW14{slash}K12-PadP$11)") (class "Default")
      (node (ref "U1") (pin "P$11") (pinfunction "ROW14/K12_P$11") (pintype "bidirectional"))
    )
  )
)
